# Badge_V3.net
KiCad netlist of a schematic drawn in EAGLE
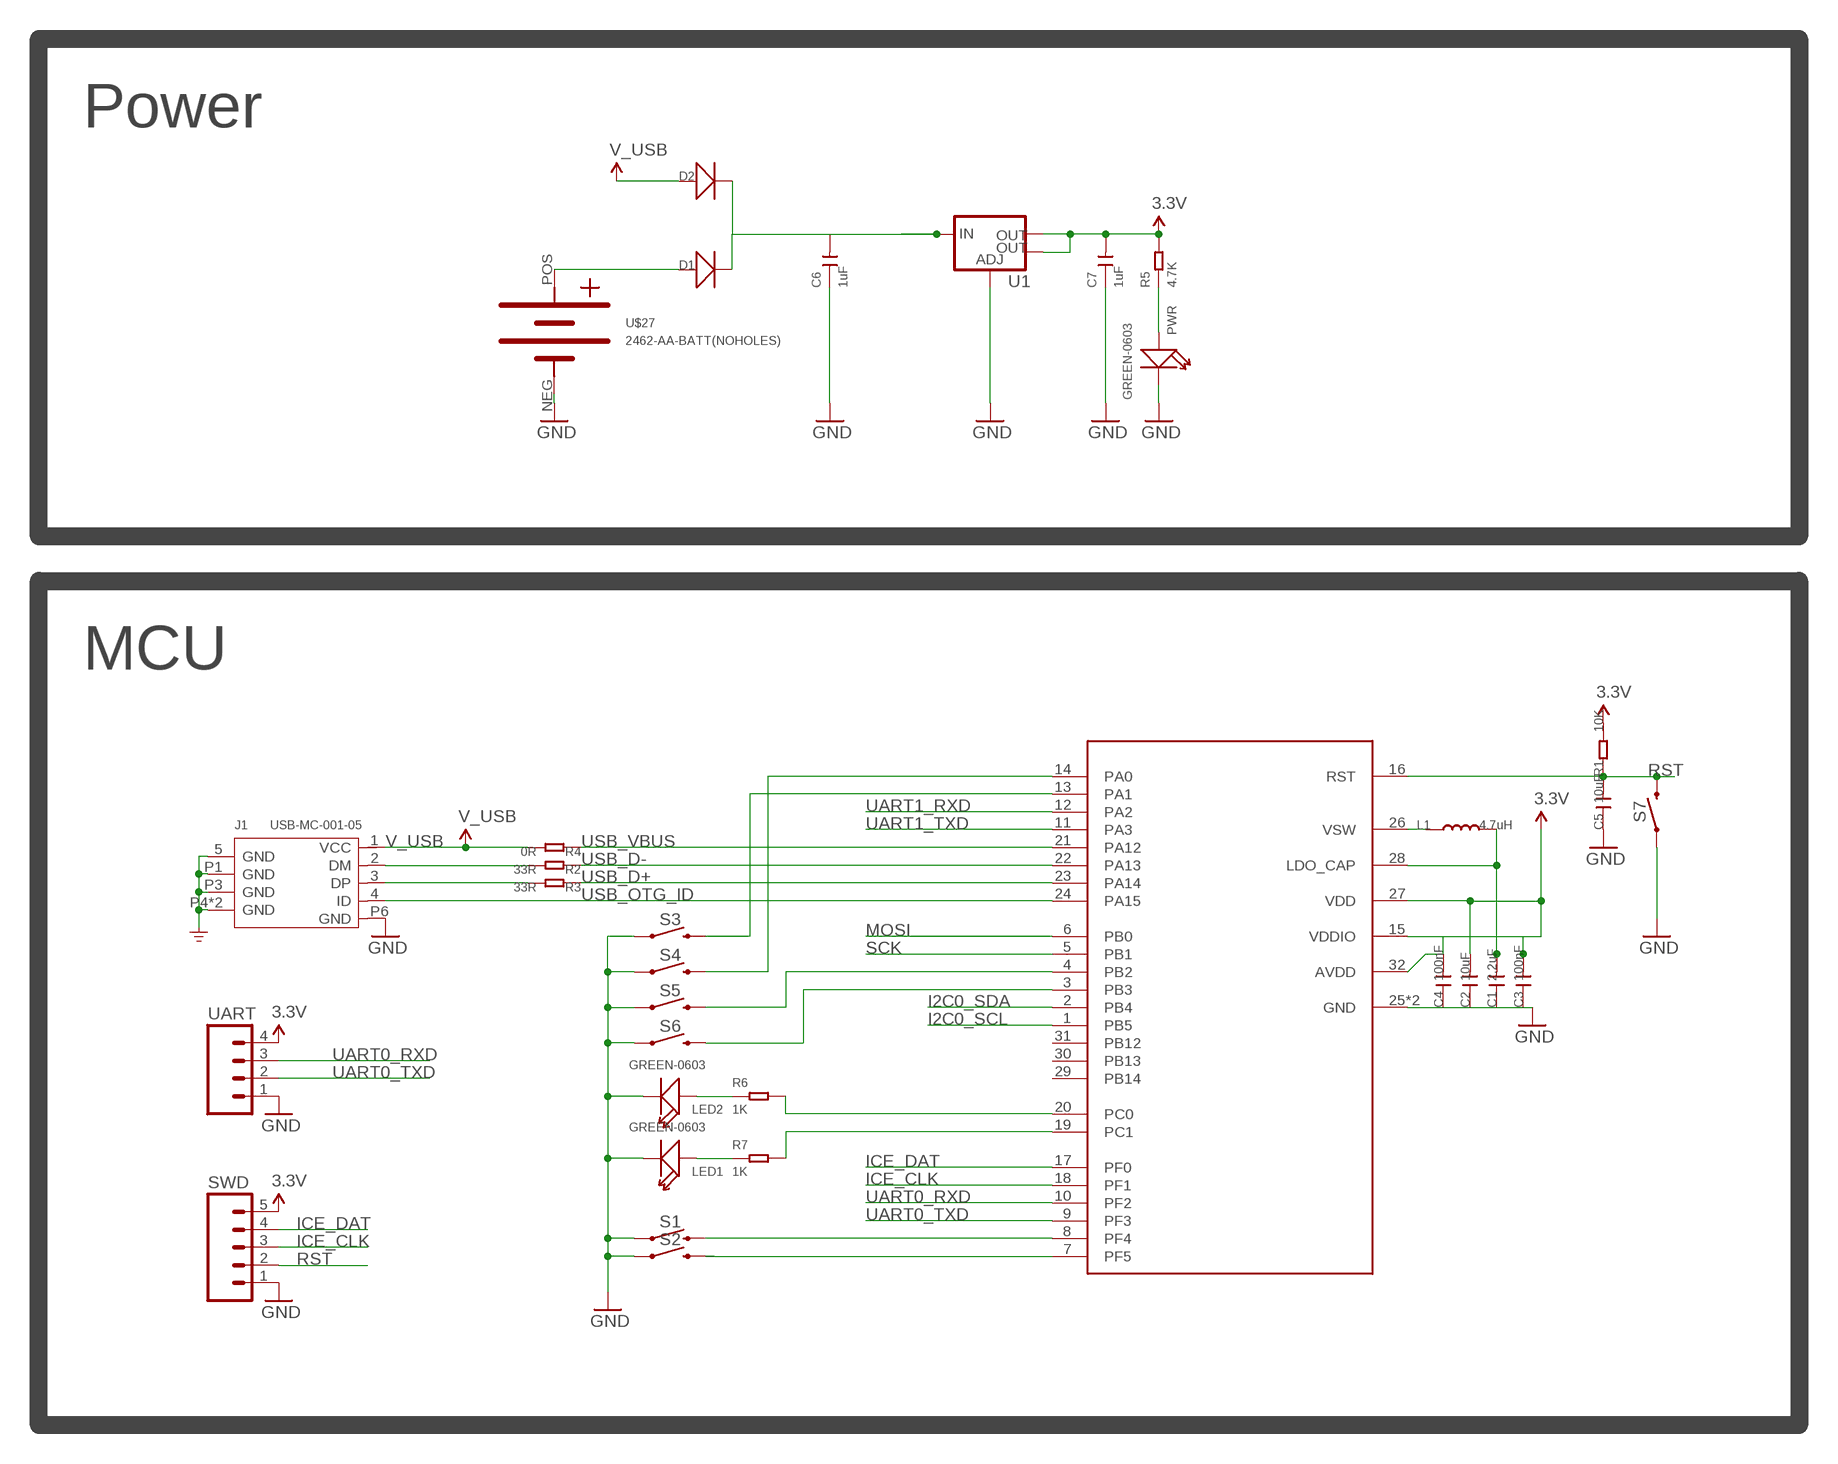
[diagram p0: schematic, sheet 1, part 1 of 2]
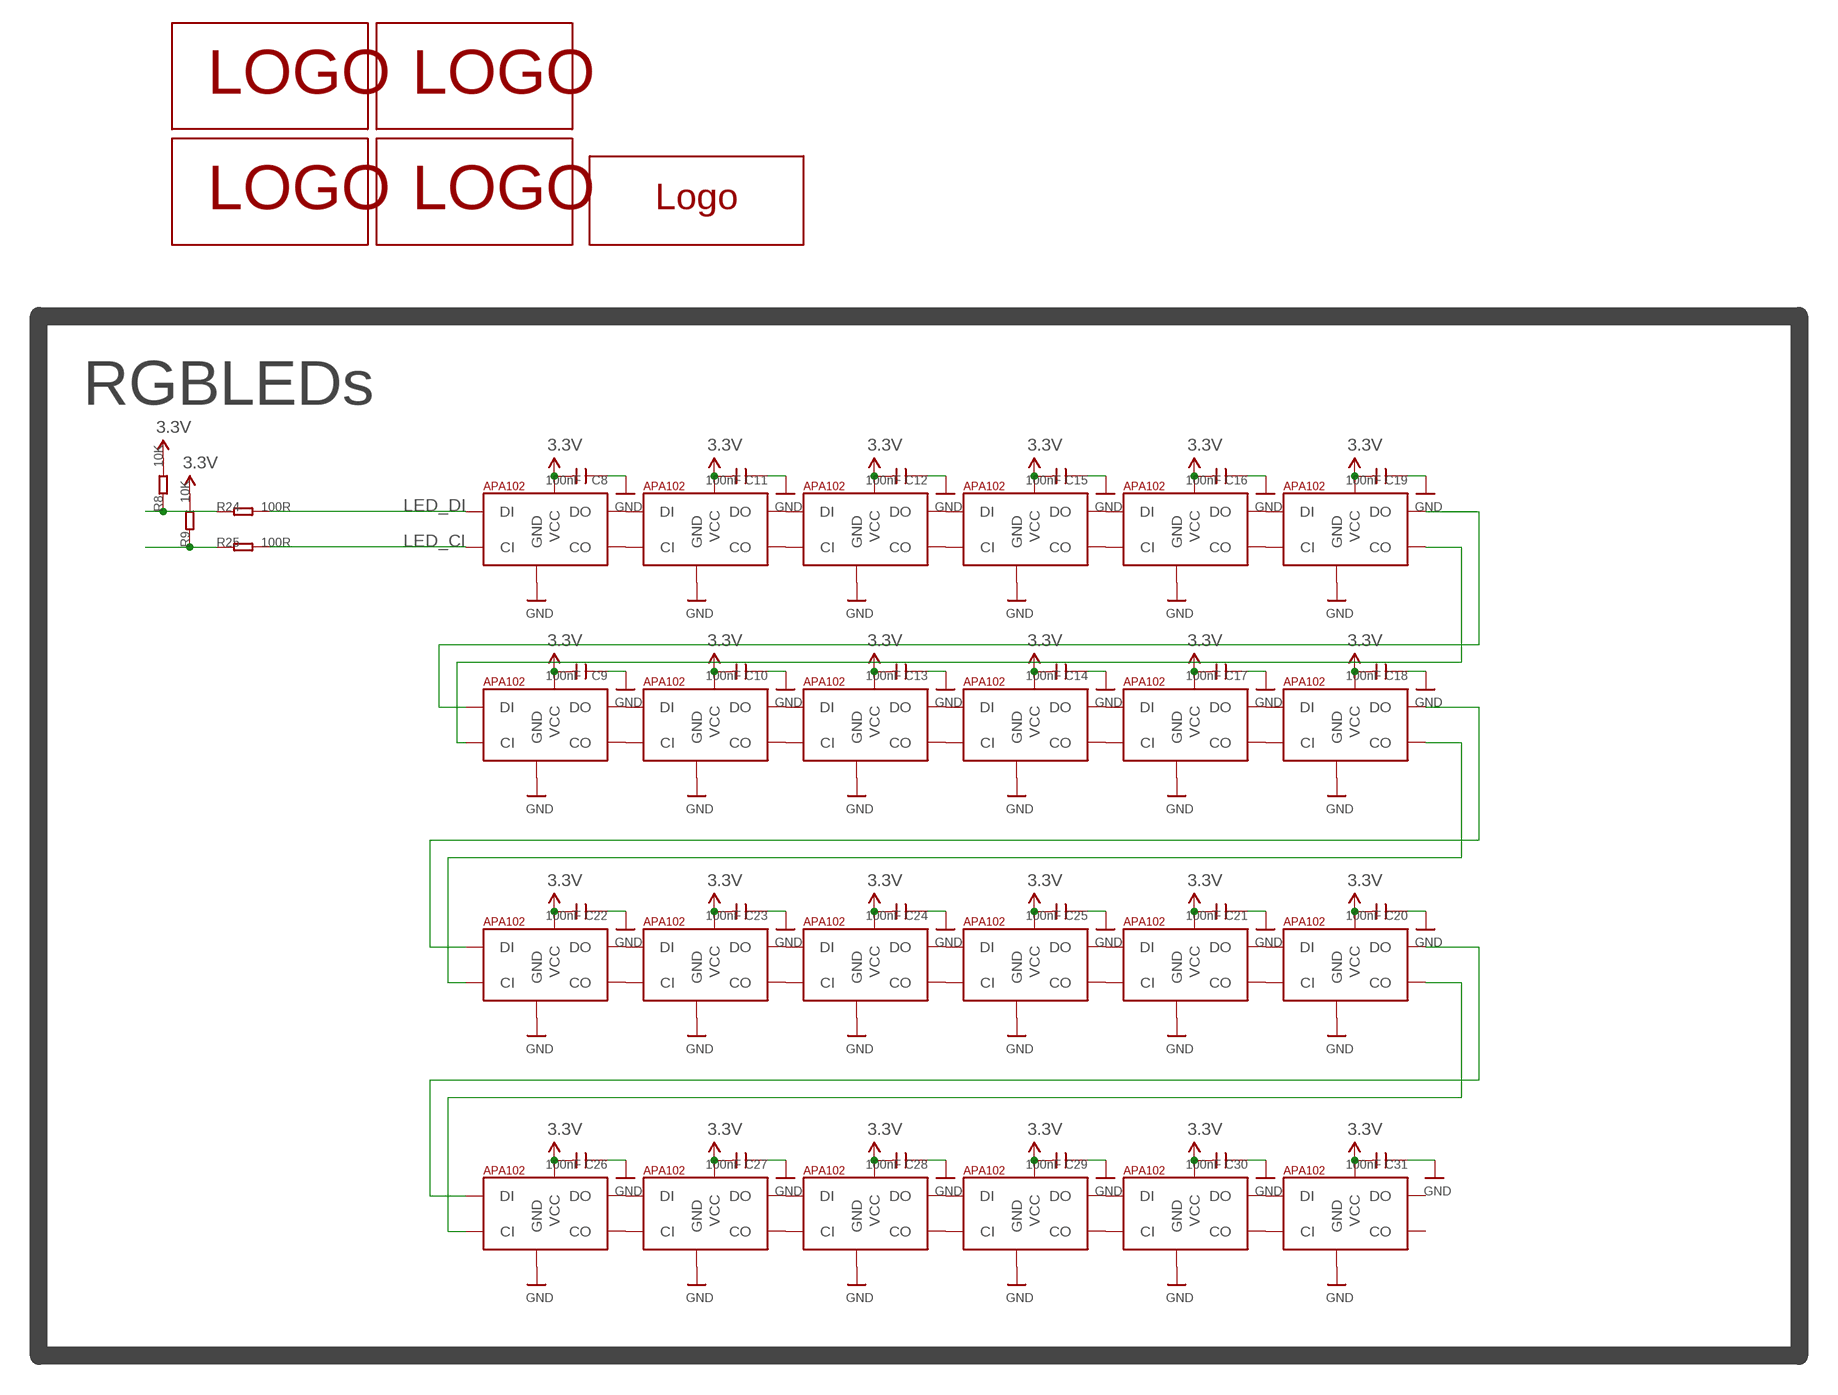
[diagram p1: schematic, sheet 1, part 2 of 2]

(export (version "E")
  (design (tool "Eeschema 10.0.6"))
  (components
    (comp (ref "C1")
      (value "2.2uF")
      (footprint "eagle-import:C0402@1")
      (libsource (lib "eagle-import") (part "C-0402"))
    )
    (comp (ref "C2")
      (value "10uF")
      (footprint "eagle-import:C0402@1")
      (libsource (lib "eagle-import") (part "C-0402"))
    )
    (comp (ref "C3")
      (value "100nF")
      (footprint "eagle-import:C0603@1")
      (libsource (lib "eagle-import") (part "C-0603"))
    )
    (comp (ref "C4")
      (value "100nF")
      (footprint "eagle-import:C0402@1")
      (libsource (lib "eagle-import") (part "C-0402"))
    )
    (comp (ref "C5")
      (value "10uF")
      (footprint "eagle-import:C0402@1")
      (libsource (lib "eagle-import") (part "C-0402"))
    )
    (comp (ref "C6")
      (value "1uF")
      (footprint "eagle-import:C0603")
      (libsource (lib "eagle-import") (part "CAP-0603"))
    )
    (comp (ref "C7")
      (value "1uF")
      (footprint "eagle-import:C0603")
      (libsource (lib "eagle-import") (part "CAP-0603"))
    )
    (comp (ref "C8")
      (value "100nF")
      (footprint "eagle-import:C0402@1")
      (libsource (lib "eagle-import") (part "C-0402"))
    )
    (comp (ref "C9")
      (value "100nF")
      (footprint "eagle-import:C0402@1")
      (libsource (lib "eagle-import") (part "C-0402"))
    )
    (comp (ref "C10")
      (value "100nF")
      (footprint "eagle-import:C0402@1")
      (libsource (lib "eagle-import") (part "C-0402"))
    )
    (comp (ref "C11")
      (value "100nF")
      (footprint "eagle-import:C0402@1")
      (libsource (lib "eagle-import") (part "C-0402"))
    )
    (comp (ref "C12")
      (value "100nF")
      (footprint "eagle-import:C0402@1")
      (libsource (lib "eagle-import") (part "C-0402"))
    )
    (comp (ref "C13")
      (value "100nF")
      (footprint "eagle-import:C0402@1")
      (libsource (lib "eagle-import") (part "C-0402"))
    )
    (comp (ref "C14")
      (value "100nF")
      (footprint "eagle-import:C0402@1")
      (libsource (lib "eagle-import") (part "C-0402"))
    )
    (comp (ref "C15")
      (value "100nF")
      (footprint "eagle-import:C0402@1")
      (libsource (lib "eagle-import") (part "C-0402"))
    )
    (comp (ref "C16")
      (value "100nF")
      (footprint "eagle-import:C0402@1")
      (libsource (lib "eagle-import") (part "C-0402"))
    )
    (comp (ref "C17")
      (value "100nF")
      (footprint "eagle-import:C0402@1")
      (libsource (lib "eagle-import") (part "C-0402"))
    )
    (comp (ref "C18")
      (value "100nF")
      (footprint "eagle-import:C0402@1")
      (libsource (lib "eagle-import") (part "C-0402"))
    )
    (comp (ref "C19")
      (value "100nF")
      (footprint "eagle-import:C0402@1")
      (libsource (lib "eagle-import") (part "C-0402"))
    )
    (comp (ref "C20")
      (value "100nF")
      (footprint "eagle-import:C0402@1")
      (libsource (lib "eagle-import") (part "C-0402"))
    )
    (comp (ref "C21")
      (value "100nF")
      (footprint "eagle-import:C0402@1")
      (libsource (lib "eagle-import") (part "C-0402"))
    )
    (comp (ref "C22")
      (value "100nF")
      (footprint "eagle-import:C0402@1")
      (libsource (lib "eagle-import") (part "C-0402"))
    )
    (comp (ref "C23")
      (value "100nF")
      (footprint "eagle-import:C0402@1")
      (libsource (lib "eagle-import") (part "C-0402"))
    )
    (comp (ref "C24")
      (value "100nF")
      (footprint "eagle-import:C0402@1")
      (libsource (lib "eagle-import") (part "C-0402"))
    )
    (comp (ref "C25")
      (value "100nF")
      (footprint "eagle-import:C0402@1")
      (libsource (lib "eagle-import") (part "C-0402"))
    )
    (comp (ref "C26")
      (value "100nF")
      (footprint "eagle-import:C0402@1")
      (libsource (lib "eagle-import") (part "C-0402"))
    )
    (comp (ref "C27")
      (value "100nF")
      (footprint "eagle-import:C0402@1")
      (libsource (lib "eagle-import") (part "C-0402"))
    )
    (comp (ref "C28")
      (value "100nF")
      (footprint "eagle-import:C0402@1")
      (libsource (lib "eagle-import") (part "C-0402"))
    )
    (comp (ref "C29")
      (value "100nF")
      (footprint "eagle-import:C0402@1")
      (libsource (lib "eagle-import") (part "C-0402"))
    )
    (comp (ref "C30")
      (value "100nF")
      (footprint "eagle-import:C0402@1")
      (libsource (lib "eagle-import") (part "C-0402"))
    )
    (comp (ref "C31")
      (value "100nF")
      (footprint "eagle-import:C0402@1")
      (libsource (lib "eagle-import") (part "C-0402"))
    )
    (comp (ref "D1")
      (value "D'1206'")
      (footprint "eagle-import:SOD123")
      (libsource (lib "eagle-import") (part "D'1206'"))
    )
    (comp (ref "D2")
      (value "D'1206'")
      (footprint "eagle-import:SOD123")
      (libsource (lib "eagle-import") (part "D'1206'"))
    )
    (comp (ref "J1")
      (value "USB-MC-001-05")
      (footprint "eagle-import:MICRO-USB5+5P-SMD-0.65-7.2X5.06MM")
      (libsource (lib "eagle-import") (part "MICRO-USB5+4P"))
    )
    (comp (ref "L1")
      (value "4.7uH")
      (footprint "eagle-import:L0603")
      (libsource (lib "eagle-import") (part "L'0603'"))
    )
    (comp (ref "LED1")
      (value "GREEN-0603")
      (footprint "eagle-import:LED-0603")
      (fields (field (name "MPN") "19-217-G7C-AN1P2-3T"))
      (libsource (lib "eagle-import") (part "SMD-LED-CLEAR-GREEN(0603)"))
    )
    (comp (ref "LED2")
      (value "GREEN-0603")
      (footprint "eagle-import:LED-0603")
      (fields (field (name "MPN") "19-217-G7C-AN1P2-3T"))
      (libsource (lib "eagle-import") (part "SMD-LED-CLEAR-GREEN(0603)"))
    )
    (comp (ref "PWR")
      (value "GREEN-0603")
      (footprint "eagle-import:LED-0603")
      (fields (field (name "MPN") "19-217-G7C-AN1P2-3T"))
      (libsource (lib "eagle-import") (part "SMD-LED-CLEAR-GREEN(0603)"))
    )
    (comp (ref "R1")
      (value "10K")
      (footprint "eagle-import:R0402")
      (libsource (lib "eagle-import") (part "R-0402"))
    )
    (comp (ref "R2")
      (value "33R")
      (footprint "eagle-import:R0402")
      (libsource (lib "eagle-import") (part "R-0402"))
    )
    (comp (ref "R3")
      (value "33R")
      (footprint "eagle-import:R0402")
      (libsource (lib "eagle-import") (part "R-0402"))
    )
    (comp (ref "R4")
      (value "0R")
      (footprint "eagle-import:R0402")
      (libsource (lib "eagle-import") (part "R-0402"))
    )
    (comp (ref "R5")
      (value "4.7K")
      (footprint "eagle-import:R0402")
      (libsource (lib "eagle-import") (part "RES-0402"))
    )
    (comp (ref "R6")
      (value "1K")
      (footprint "eagle-import:R0402")
      (libsource (lib "eagle-import") (part "RES-0402"))
    )
    (comp (ref "R7")
      (value "1K")
      (footprint "eagle-import:R0402")
      (libsource (lib "eagle-import") (part "RES-0402"))
    )
    (comp (ref "R8")
      (value "10K")
      (footprint "eagle-import:R0402")
      (libsource (lib "eagle-import") (part "R-0402"))
    )
    (comp (ref "R9")
      (value "10K")
      (footprint "eagle-import:R0402")
      (libsource (lib "eagle-import") (part "R-0402"))
    )
    (comp (ref "R24")
      (value "100R")
      (footprint "eagle-import:R0402")
      (libsource (lib "eagle-import") (part "R-0402"))
    )
    (comp (ref "R25")
      (value "100R")
      (footprint "eagle-import:R0402")
      (libsource (lib "eagle-import") (part "R-0402"))
    )
    (comp (ref "S1")
      (value "MOMENTARY-SWITCH-SPST-SMD-6.2MM-TALL")
      (footprint "eagle-import:TACTILE_SWITCH_SMD_6.2MM_TALL")
      (libsource (lib "eagle-import") (part "MOMENTARY-SWITCH-SPST-SMD-6.2MM-TALL"))
    )
    (comp (ref "S2")
      (value "MOMENTARY-SWITCH-SPST-SMD-6.2MM-TALL")
      (footprint "eagle-import:TACTILE_SWITCH_SMD_6.2MM_TALL")
      (libsource (lib "eagle-import") (part "MOMENTARY-SWITCH-SPST-SMD-6.2MM-TALL"))
    )
    (comp (ref "S3")
      (value "MOMENTARY-SWITCH-SPST-SMD-6.2MM-TALL")
      (footprint "eagle-import:TACTILE_SWITCH_SMD_6.2MM_TALL")
      (libsource (lib "eagle-import") (part "MOMENTARY-SWITCH-SPST-SMD-6.2MM-TALL"))
    )
    (comp (ref "S4")
      (value "MOMENTARY-SWITCH-SPST-SMD-6.2MM-TALL")
      (footprint "eagle-import:TACTILE_SWITCH_SMD_6.2MM_TALL")
      (libsource (lib "eagle-import") (part "MOMENTARY-SWITCH-SPST-SMD-6.2MM-TALL"))
    )
    (comp (ref "S5")
      (value "MOMENTARY-SWITCH-SPST-SMD-6.2MM-TALL")
      (footprint "eagle-import:TACTILE_SWITCH_SMD_6.2MM_TALL")
      (libsource (lib "eagle-import") (part "MOMENTARY-SWITCH-SPST-SMD-6.2MM-TALL"))
    )
    (comp (ref "S6")
      (value "MOMENTARY-SWITCH-SPST-SMD-6.2MM-TALL")
      (footprint "eagle-import:TACTILE_SWITCH_SMD_6.2MM_TALL")
      (libsource (lib "eagle-import") (part "MOMENTARY-SWITCH-SPST-SMD-6.2MM-TALL"))
    )
    (comp (ref "S7")
      (value "MOMENTARY-SWITCH-SPST-SMD-6.2MM-TALL")
      (footprint "eagle-import:TACTILE_SWITCH_SMD_6.2MM_TALL")
      (libsource (lib "eagle-import") (part "MOMENTARY-SWITCH-SPST-SMD-6.2MM-TALL"))
    )
    (comp (ref "SWD")
      (value "M05LOCK")
      (footprint "eagle-import:1X05_LOCK")
      (libsource (lib "eagle-import") (part "M05LOCK"))
    )
    (comp (ref "U$1")
      (value "M2351")
      (footprint "eagle-import:QFN-32")
      (libsource (lib "eagle-import") (part "M2351"))
    )
    (comp (ref "U$2")
      (value "APA1022020")
      (footprint "eagle-import:APA102_2020")
      (libsource (lib "eagle-import") (part "APA1022020"))
    )
    (comp (ref "U$4")
      (value "APA1022020")
      (footprint "eagle-import:APA102_2020")
      (libsource (lib "eagle-import") (part "APA1022020"))
    )
    (comp (ref "U$5")
      (value "APA1022020")
      (footprint "eagle-import:APA102_2020")
      (libsource (lib "eagle-import") (part "APA1022020"))
    )
    (comp (ref "U$6")
      (value "APA1022020")
      (footprint "eagle-import:APA102_2020")
      (libsource (lib "eagle-import") (part "APA1022020"))
    )
    (comp (ref "U$7")
      (value "APA1022020")
      (footprint "eagle-import:APA102_2020")
      (libsource (lib "eagle-import") (part "APA1022020"))
    )
    (comp (ref "U$8")
      (value "APA1022020")
      (footprint "eagle-import:APA102_2020")
      (libsource (lib "eagle-import") (part "APA1022020"))
    )
    (comp (ref "U$9")
      (value "APA1022020")
      (footprint "eagle-import:APA102_2020")
      (libsource (lib "eagle-import") (part "APA1022020"))
    )
    (comp (ref "U$10")
      (value "APA1022020")
      (footprint "eagle-import:APA102_2020")
      (libsource (lib "eagle-import") (part "APA1022020"))
    )
    (comp (ref "U$11")
      (value "APA1022020")
      (footprint "eagle-import:APA102_2020")
      (libsource (lib "eagle-import") (part "APA1022020"))
    )
    (comp (ref "U$12")
      (value "APA1022020")
      (footprint "eagle-import:APA102_2020")
      (libsource (lib "eagle-import") (part "APA1022020"))
    )
    (comp (ref "U$13")
      (value "APA1022020")
      (footprint "eagle-import:APA102_2020")
      (libsource (lib "eagle-import") (part "APA1022020"))
    )
    (comp (ref "U$14")
      (value "APA1022020")
      (footprint "eagle-import:APA102_2020")
      (libsource (lib "eagle-import") (part "APA1022020"))
    )
    (comp (ref "U$15")
      (value "APA1022020")
      (footprint "eagle-import:APA102_2020")
      (libsource (lib "eagle-import") (part "APA1022020"))
    )
    (comp (ref "U$16")
      (value "APA1022020")
      (footprint "eagle-import:APA102_2020")
      (libsource (lib "eagle-import") (part "APA1022020"))
    )
    (comp (ref "U$17")
      (value "APA1022020")
      (footprint "eagle-import:APA102_2020")
      (libsource (lib "eagle-import") (part "APA1022020"))
    )
    (comp (ref "U$18")
      (value "APA1022020")
      (footprint "eagle-import:APA102_2020")
      (libsource (lib "eagle-import") (part "APA1022020"))
    )
    (comp (ref "U$19")
      (value "APA1022020")
      (footprint "eagle-import:APA102_2020")
      (libsource (lib "eagle-import") (part "APA1022020"))
    )
    (comp (ref "U$20")
      (value "APA1022020")
      (footprint "eagle-import:APA102_2020")
      (libsource (lib "eagle-import") (part "APA1022020"))
    )
    (comp (ref "U$21")
      (value "APA1022020")
      (footprint "eagle-import:APA102_2020")
      (libsource (lib "eagle-import") (part "APA1022020"))
    )
    (comp (ref "U$22")
      (value "APA1022020")
      (footprint "eagle-import:APA102_2020")
      (libsource (lib "eagle-import") (part "APA1022020"))
    )
    (comp (ref "U$23")
      (value "APA1022020")
      (footprint "eagle-import:APA102_2020")
      (libsource (lib "eagle-import") (part "APA1022020"))
    )
    (comp (ref "U$24")
      (value "APA1022020")
      (footprint "eagle-import:APA102_2020")
      (libsource (lib "eagle-import") (part "APA1022020"))
    )
    (comp (ref "U$25")
      (value "APA1022020")
      (footprint "eagle-import:APA102_2020")
      (libsource (lib "eagle-import") (part "APA1022020"))
    )
    (comp (ref "U$26")
      (value "TAIWANSILK_FILL")
      (footprint "eagle-import:TAIWAN_SILK_FILL")
      (libsource (lib "eagle-import") (part "TAIWANSILK_FILL"))
    )
    (comp (ref "U$27")
      (value "2462-AA-BATT(NOHOLES)")
      (footprint "eagle-import:2462-AA-BATT-NOHOLES")
      (libsource (lib "eagle-import") (part "2462-AA-BATT(NOHOLES)"))
    )
    (comp (ref "U$28")
      (value "HITCON_LOGOGOLD_LARGE")
      (footprint "eagle-import:HITCON_LOGO_BIGGER_GOLD")
      (libsource (lib "eagle-import") (part "HITCON_LOGOGOLD_LARGE"))
    )
    (comp (ref "U$30")
      (value "TAIWANKIM")
      (footprint "eagle-import:TAIWAN_SILK_FILL_2")
      (libsource (lib "eagle-import") (part "TAIWANKIM"))
    )
    (comp (ref "U$31")
      (value "TAIWANMAZ")
      (footprint "eagle-import:TAIWAN_SILK_FILL_4")
      (libsource (lib "eagle-import") (part "TAIWANMAZ"))
    )
    (comp (ref "U$33")
      (value "APA1022020")
      (footprint "eagle-import:APA102_2020")
      (libsource (lib "eagle-import") (part "APA1022020"))
    )
    (comp (ref "U$34")
      (value "TAIWANPUN")
      (footprint "eagle-import:TAIWAN_SILK_FILL_3")
      (libsource (lib "eagle-import") (part "TAIWANPUN"))
    )
    (comp (ref "U1")
      (value "V_REG_LM1117SOT223")
      (footprint "eagle-import:SOT223")
      (libsource (lib "eagle-import") (part "V_REG_LM1117SOT223"))
    )
    (comp (ref "UART")
      (value "M04LOCK")
      (footprint "eagle-import:1X04_LOCK")
      (libsource (lib "eagle-import") (part "M04LOCK"))
    )
  )
  (nets
    (net (code "1") (name "/I2C0_SCL") (class "Default")
      (node (ref "U$1") (pin "1") (pinfunction "PB5_1") (pintype "bidirectional"))
    )
    (net (code "2") (name "/I2C0_SDA") (class "Default")
      (node (ref "U$1") (pin "2") (pinfunction "PB4_2") (pintype "bidirectional"))
    )
    (net (code "3") (name "/ICE_CLK") (class "Default")
      (node (ref "SWD") (pin "3") (pinfunction "3_3") (pintype "passive"))
      (node (ref "U$1") (pin "18") (pinfunction "PF1_18") (pintype "bidirectional"))
    )
    (net (code "4") (name "/ICE_DAT") (class "Default")
      (node (ref "SWD") (pin "4") (pinfunction "4_4") (pintype "passive"))
      (node (ref "U$1") (pin "17") (pinfunction "PF0_17") (pintype "bidirectional"))
    )
    (net (code "5") (name "/LED_CI") (class "Default")
      (node (ref "R25") (pin "2") (pinfunction "2_2") (pintype "passive"))
      (node (ref "U$33") (pin "C_IN") (pinfunction "CI_C_IN") (pintype "bidirectional"))
    )
    (net (code "6") (name "/LED_DI") (class "Default")
      (node (ref "R24") (pin "2") (pinfunction "2_2") (pintype "passive"))
      (node (ref "U$33") (pin "D_IN") (pinfunction "DI_D_IN") (pintype "bidirectional"))
    )
    (net (code "7") (name "/MOSI") (class "Default")
      (node (ref "R24") (pin "1") (pinfunction "1_1") (pintype "passive"))
      (node (ref "R8") (pin "1") (pinfunction "1_1") (pintype "passive"))
      (node (ref "U$1") (pin "6") (pinfunction "PB0_6") (pintype "bidirectional"))
    )
    (net (code "8") (name "/RST") (class "Default")
      (node (ref "C5") (pin "2") (pinfunction "2_2") (pintype "passive"))
      (node (ref "R1") (pin "1") (pinfunction "1_1") (pintype "passive"))
      (node (ref "S7") (pin "B2") (pinfunction "2_B2") (pintype "passive"))
      (node (ref "SWD") (pin "2") (pinfunction "2_2") (pintype "passive"))
      (node (ref "U$1") (pin "16") (pinfunction "RST_16") (pintype "bidirectional"))
    )
    (net (code "9") (name "/SCK") (class "Default")
      (node (ref "R25") (pin "1") (pinfunction "1_1") (pintype "passive"))
      (node (ref "R9") (pin "1") (pinfunction "1_1") (pintype "passive"))
      (node (ref "U$1") (pin "5") (pinfunction "PB1_5") (pintype "bidirectional"))
    )
    (net (code "10") (name "/UART0_RXD") (class "Default")
      (node (ref "U$1") (pin "10") (pinfunction "PF2_10") (pintype "bidirectional"))
      (node (ref "UART") (pin "3") (pinfunction "3_3") (pintype "passive"))
    )
    (net (code "11") (name "/UART0_TXD") (class "Default")
      (node (ref "U$1") (pin "9") (pinfunction "PF3_9") (pintype "bidirectional"))
      (node (ref "UART") (pin "2") (pinfunction "2_2") (pintype "passive"))
    )
    (net (code "12") (name "/UART1_RXD") (class "Default")
      (node (ref "U$1") (pin "12") (pinfunction "PA2_12") (pintype "bidirectional"))
    )
    (net (code "13") (name "/UART1_TXD") (class "Default")
      (node (ref "U$1") (pin "11") (pinfunction "PA3_11") (pintype "bidirectional"))
    )
    (net (code "14") (name "/USB_D+") (class "Default")
      (node (ref "R3") (pin "1") (pinfunction "1_1") (pintype "passive"))
      (node (ref "U$1") (pin "23") (pinfunction "PA14_23") (pintype "bidirectional"))
    )
    (net (code "15") (name "/USB_D-") (class "Default")
      (node (ref "R2") (pin "1") (pinfunction "1_1") (pintype "passive"))
      (node (ref "U$1") (pin "22") (pinfunction "PA13_22") (pintype "bidirectional"))
    )
    (net (code "16") (name "/USB_OTG_ID") (class "Default")
      (node (ref "J1") (pin "4") (pinfunction "ID_4") (pintype "bidirectional"))
      (node (ref "U$1") (pin "24") (pinfunction "PA15_24") (pintype "bidirectional"))
    )
    (net (code "17") (name "/USB_VBUS") (class "Default")
      (node (ref "R4") (pin "1") (pinfunction "1_1") (pintype "passive"))
      (node (ref "U$1") (pin "21") (pinfunction "PA12_21") (pintype "bidirectional"))
    )
    (net (code "18") (name "3.3V") (class "Default")
      (node (ref "C10") (pin "2") (pinfunction "2_2") (pintype "passive"))
      (node (ref "C11") (pin "2") (pinfunction "2_2") (pintype "passive"))
      (node (ref "C12") (pin "2") (pinfunction "2_2") (pintype "passive"))
      (node (ref "C13") (pin "2") (pinfunction "2_2") (pintype "passive"))
      (node (ref "C14") (pin "2") (pinfunction "2_2") (pintype "passive"))
      (node (ref "C15") (pin "2") (pinfunction "2_2") (pintype "passive"))
      (node (ref "C16") (pin "2") (pinfunction "2_2") (pintype "passive"))
      (node (ref "C17") (pin "2") (pinfunction "2_2") (pintype "passive"))
      (node (ref "C18") (pin "2") (pinfunction "2_2") (pintype "passive"))
      (node (ref "C19") (pin "2") (pinfunction "2_2") (pintype "passive"))
      (node (ref "C2") (pin "2") (pinfunction "2_2") (pintype "passive"))
      (node (ref "C20") (pin "2") (pinfunction "2_2") (pintype "passive"))
      (node (ref "C21") (pin "2") (pinfunction "2_2") (pintype "passive"))
      (node (ref "C22") (pin "2") (pinfunction "2_2") (pintype "passive"))
      (node (ref "C23") (pin "2") (pinfunction "2_2") (pintype "passive"))
      (node (ref "C24") (pin "2") (pinfunction "2_2") (pintype "passive"))
      (node (ref "C25") (pin "2") (pinfunction "2_2") (pintype "passive"))
      (node (ref "C26") (pin "2") (pinfunction "2_2") (pintype "passive"))
      (node (ref "C27") (pin "2") (pinfunction "2_2") (pintype "passive"))
      (node (ref "C28") (pin "2") (pinfunction "2_2") (pintype "passive"))
      (node (ref "C29") (pin "2") (pinfunction "2_2") (pintype "passive"))
      (node (ref "C3") (pin "2") (pinfunction "2_2") (pintype "passive"))
      (node (ref "C30") (pin "2") (pinfunction "2_2") (pintype "passive"))
      (node (ref "C31") (pin "2") (pinfunction "2_2") (pintype "passive"))
      (node (ref "C4") (pin "2") (pinfunction "2_2") (pintype "passive"))
      (node (ref "C7") (pin "2") (pinfunction "2_2") (pintype "passive"))
      (node (ref "C8") (pin "2") (pinfunction "2_2") (pintype "passive"))
      (node (ref "C9") (pin "2") (pinfunction "2_2") (pintype "passive"))
      (node (ref "R1") (pin "2") (pinfunction "2_2") (pintype "passive"))
      (node (ref "R5") (pin "2") (pinfunction "2_2") (pintype "passive"))
      (node (ref "R8") (pin "2") (pinfunction "2_2") (pintype "passive"))
      (node (ref "R9") (pin "2") (pinfunction "2_2") (pintype "passive"))
      (node (ref "SWD") (pin "5") (pinfunction "5_5") (pintype "passive"))
      (node (ref "U$1") (pin "15") (pinfunction "VDDIO_15") (pintype "bidirectional"))
      (node (ref "U$1") (pin "27") (pinfunction "VDD_27") (pintype "bidirectional"))
      (node (ref "U$1") (pin "32") (pinfunction "AVDD_32") (pintype "bidirectional"))
      (node (ref "U$10") (pin "V_CC") (pinfunction "VCC_V_CC") (pintype "bidirectional"))
      (node (ref "U$11") (pin "V_CC") (pinfunction "VCC_V_CC") (pintype "bidirectional"))
      (node (ref "U$12") (pin "V_CC") (pinfunction "VCC_V_CC") (pintype "bidirectional"))
      (node (ref "U$13") (pin "V_CC") (pinfunction "VCC_V_CC") (pintype "bidirectional"))
      (node (ref "U$14") (pin "V_CC") (pinfunction "VCC_V_CC") (pintype "bidirectional"))
      (node (ref "U$15") (pin "V_CC") (pinfunction "VCC_V_CC") (pintype "bidirectional"))
      (node (ref "U$16") (pin "V_CC") (pinfunction "VCC_V_CC") (pintype "bidirectional"))
      (node (ref "U$17") (pin "V_CC") (pinfunction "VCC_V_CC") (pintype "bidirectional"))
      (node (ref "U$18") (pin "V_CC") (pinfunction "VCC_V_CC") (pintype "bidirectional"))
      (node (ref "U$19") (pin "V_CC") (pinfunction "VCC_V_CC") (pintype "bidirectional"))
      (node (ref "U$2") (pin "V_CC") (pinfunction "VCC_V_CC") (pintype "bidirectional"))
      (node (ref "U$20") (pin "V_CC") (pinfunction "VCC_V_CC") (pintype "bidirectional"))
      (node (ref "U$21") (pin "V_CC") (pinfunction "VCC_V_CC") (pintype "bidirectional"))
      (node (ref "U$22") (pin "V_CC") (pinfunction "VCC_V_CC") (pintype "bidirectional"))
      (node (ref "U$23") (pin "V_CC") (pinfunction "VCC_V_CC") (pintype "bidirectional"))
      (node (ref "U$24") (pin "V_CC") (pinfunction "VCC_V_CC") (pintype "bidirectional"))
      (node (ref "U$25") (pin "V_CC") (pinfunction "VCC_V_CC") (pintype "bidirectional"))
      (node (ref "U$33") (pin "V_CC") (pinfunction "VCC_V_CC") (pintype "bidirectional"))
      (node (ref "U$4") (pin "V_CC") (pinfunction "VCC_V_CC") (pintype "bidirectional"))
      (node (ref "U$5") (pin "V_CC") (pinfunction "VCC_V_CC") (pintype "bidirectional"))
      (node (ref "U$6") (pin "V_CC") (pinfunction "VCC_V_CC") (pintype "bidirectional"))
      (node (ref "U$7") (pin "V_CC") (pinfunction "VCC_V_CC") (pintype "bidirectional"))
      (node (ref "U$8") (pin "V_CC") (pinfunction "VCC_V_CC") (pintype "bidirectional"))
      (node (ref "U$9") (pin "V_CC") (pinfunction "VCC_V_CC") (pintype "bidirectional"))
      (node (ref "U1") (pin "2") (pinfunction "OUT_2") (pintype "output"))
      (node (ref "U1") (pin "4") (pinfunction "OUT_4") (pintype "output"))
      (node (ref "UART") (pin "4") (pinfunction "4_4") (pintype "passive"))
    )
    (net (code "19") (name "GND") (class "Default")
      (node (ref "C1") (pin "1") (pinfunction "1_1") (pintype "passive"))
      (node (ref "C10") (pin "1") (pinfunction "1_1") (pintype "passive"))
      (node (ref "C11") (pin "1") (pinfunction "1_1") (pintype "passive"))
      (node (ref "C12") (pin "1") (pinfunction "1_1") (pintype "passive"))
      (node (ref "C13") (pin "1") (pinfunction "1_1") (pintype "passive"))
      (node (ref "C14") (pin "1") (pinfunction "1_1") (pintype "passive"))
      (node (ref "C15") (pin "1") (pinfunction "1_1") (pintype "passive"))
      (node (ref "C16") (pin "1") (pinfunction "1_1") (pintype "passive"))
      (node (ref "C17") (pin "1") (pinfunction "1_1") (pintype "passive"))
      (node (ref "C18") (pin "1") (pinfunction "1_1") (pintype "passive"))
      (node (ref "C19") (pin "1") (pinfunction "1_1") (pintype "passive"))
      (node (ref "C2") (pin "1") (pinfunction "1_1") (pintype "passive"))
      (node (ref "C20") (pin "1") (pinfunction "1_1") (pintype "passive"))
      (node (ref "C21") (pin "1") (pinfunction "1_1") (pintype "passive"))
      (node (ref "C22") (pin "1") (pinfunction "1_1") (pintype "passive"))
      (node (ref "C23") (pin "1") (pinfunction "1_1") (pintype "passive"))
      (node (ref "C24") (pin "1") (pinfunction "1_1") (pintype "passive"))
      (node (ref "C25") (pin "1") (pinfunction "1_1") (pintype "passive"))
      (node (ref "C26") (pin "1") (pinfunction "1_1") (pintype "passive"))
      (node (ref "C27") (pin "1") (pinfunction "1_1") (pintype "passive"))
      (node (ref "C28") (pin "1") (pinfunction "1_1") (pintype "passive"))
      (node (ref "C29") (pin "1") (pinfunction "1_1") (pintype "passive"))
      (node (ref "C3") (pin "1") (pinfunction "1_1") (pintype "passive"))
      (node (ref "C30") (pin "1") (pinfunction "1_1") (pintype "passive"))
      (node (ref "C31") (pin "1") (pinfunction "1_1") (pintype "passive"))
      (node (ref "C4") (pin "1") (pinfunction "1_1") (pintype "passive"))
      (node (ref "C5") (pin "1") (pinfunction "1_1") (pintype "passive"))
      (node (ref "C6") (pin "1") (pinfunction "1_1") (pintype "passive"))
      (node (ref "C7") (pin "1") (pinfunction "1_1") (pintype "passive"))
      (node (ref "C8") (pin "1") (pinfunction "1_1") (pintype "passive"))
      (node (ref "C9") (pin "1") (pinfunction "1_1") (pintype "passive"))
      (node (ref "J1") (pin "5") (pinfunction "GND_5") (pintype "bidirectional"))
      (node (ref "J1") (pin "P1") (pinfunction "GND_P1") (pintype "bidirectional"))
      (node (ref "J1") (pin "P3") (pinfunction "GND_P3") (pintype "bidirectional"))
      (node (ref "J1") (pin "P4") (pinfunction "GND_P4") (pintype "bidirectional"))
      (node (ref "J1") (pin "P5") (pinfunction "GND_P5") (pintype "bidirectional"))
      (node (ref "J1") (pin "P6") (pinfunction "GND_P6") (pintype "bidirectional"))
      (node (ref "LED1") (pin "-") (pinfunction "-_-") (pintype "passive"))
      (node (ref "LED2") (pin "-") (pinfunction "-_-") (pintype "passive"))
      (node (ref "PWR") (pin "-") (pinfunction "-_-") (pintype "passive"))
      (node (ref "S1") (pin "A2") (pinfunction "1_A2") (pintype "passive"))
      (node (ref "S2") (pin "A2") (pinfunction "1_A2") (pintype "passive"))
      (node (ref "S3") (pin "A2") (pinfunction "1_A2") (pintype "passive"))
      (node (ref "S4") (pin "A2") (pinfunction "1_A2") (pintype "passive"))
      (node (ref "S5") (pin "A2") (pinfunction "1_A2") (pintype "passive"))
      (node (ref "S6") (pin "A2") (pinfunction "1_A2") (pintype "passive"))
      (node (ref "S7") (pin "A2") (pinfunction "1_A2") (pintype "passive"))
      (node (ref "SWD") (pin "1") (pinfunction "1_1") (pintype "passive"))
      (node (ref "U$1") (pin "25") (pinfunction "GND_25") (pintype "bidirectional"))
      (node (ref "U$1") (pin "EP") (pinfunction "GND_EP") (pintype "bidirectional"))
      (node (ref "U$10") (pin "GND") (pinfunction "GND_GND") (pintype "bidirectional"))
      (node (ref "U$11") (pin "GND") (pinfunction "GND_GND") (pintype "bidirectional"))
      (node (ref "U$12") (pin "GND") (pinfunction "GND_GND") (pintype "bidirectional"))
      (node (ref "U$13") (pin "GND") (pinfunction "GND_GND") (pintype "bidirectional"))
      (node (ref "U$14") (pin "GND") (pinfunction "GND_GND") (pintype "bidirectional"))
      (node (ref "U$15") (pin "GND") (pinfunction "GND_GND") (pintype "bidirectional"))
      (node (ref "U$16") (pin "GND") (pinfunction "GND_GND") (pintype "bidirectional"))
      (node (ref "U$17") (pin "GND") (pinfunction "GND_GND") (pintype "bidirectional"))
      (node (ref "U$18") (pin "GND") (pinfunction "GND_GND") (pintype "bidirectional"))
      (node (ref "U$19") (pin "GND") (pinfunction "GND_GND") (pintype "bidirectional"))
      (node (ref "U$2") (pin "GND") (pinfunction "GND_GND") (pintype "bidirectional"))
      (node (ref "U$20") (pin "GND") (pinfunction "GND_GND") (pintype "bidirectional"))
      (node (ref "U$21") (pin "GND") (pinfunction "GND_GND") (pintype "bidirectional"))
      (node (ref "U$22") (pin "GND") (pinfunction "GND_GND") (pintype "bidirectional"))
      (node (ref "U$23") (pin "GND") (pinfunction "GND_GND") (pintype "bidirectional"))
      (node (ref "U$24") (pin "GND") (pinfunction "GND_GND") (pintype "bidirectional"))
      (node (ref "U$25") (pin "GND") (pinfunction "GND_GND") (pintype "bidirectional"))
      (node (ref "U$27") (pin "NEG") (pinfunction "NEG_NEG") (pintype "bidirectional"))
      (node (ref "U$33") (pin "GND") (pinfunction "GND_GND") (pintype "bidirectional"))
      (node (ref "U$4") (pin "GND") (pinfunction "GND_GND") (pintype "bidirectional"))
      (node (ref "U$5") (pin "GND") (pinfunction "GND_GND") (pintype "bidirectional"))
      (node (ref "U$6") (pin "GND") (pinfunction "GND_GND") (pintype "bidirectional"))
      (node (ref "U$7") (pin "GND") (pinfunction "GND_GND") (pintype "bidirectional"))
      (node (ref "U$8") (pin "GND") (pinfunction "GND_GND") (pintype "bidirectional"))
      (node (ref "U$9") (pin "GND") (pinfunction "GND_GND") (pintype "bidirectional"))
      (node (ref "U1") (pin "1") (pinfunction "ADJ_1") (pintype "input"))
      (node (ref "UART") (pin "1") (pinfunction "1_1") (pintype "passive"))
    )
    (net (code "20") (name "Net-(D1-Pad+)") (class "Default")
      (node (ref "D1") (pin "+") (pinfunction "+_+") (pintype "passive"))
      (node (ref "U$27") (pin "POS") (pinfunction "POS_POS") (pintype "bidirectional"))
    )
    (net (code "21") (name "Net-(J1-DM)") (class "Default")
      (node (ref "J1") (pin "2") (pinfunction "DM_2") (pintype "bidirectional"))
      (node (ref "R2") (pin "2") (pinfunction "2_2") (pintype "passive"))
    )
    (net (code "22") (name "Net-(J1-DP)") (class "Default")
      (node (ref "J1") (pin "3") (pinfunction "DP_3") (pintype "bidirectional"))
      (node (ref "R3") (pin "2") (pinfunction "2_2") (pintype "passive"))
    )
    (net (code "23") (name "Net-(LED1-Pad+)") (class "Default")
      (node (ref "LED1") (pin "+") (pinfunction "+_+") (pintype "passive"))
      (node (ref "R7") (pin "1") (pinfunction "1_1") (pintype "passive"))
    )
    (net (code "24") (name "Net-(LED2-Pad+)") (class "Default")
      (node (ref "LED2") (pin "+") (pinfunction "+_+") (pintype "passive"))
      (node (ref "R6") (pin "1") (pinfunction "1_1") (pintype "passive"))
    )
    (net (code "25") (name "Net-(PWR-Pad+)") (class "Default")
      (node (ref "PWR") (pin "+") (pinfunction "+_+") (pintype "passive"))
      (node (ref "R5") (pin "1") (pinfunction "1_1") (pintype "passive"))
    )
    (net (code "26") (name "Net-(S1-2)") (class "Default")
      (node (ref "S1") (pin "B2") (pinfunction "2_B2") (pintype "passive"))
      (node (ref "U$1") (pin "8") (pinfunction "PF4_8") (pintype "bidirectional"))
    )
    (net (code "27") (name "Net-(S2-2)") (class "Default")
      (node (ref "S2") (pin "B2") (pinfunction "2_B2") (pintype "passive"))
      (node (ref "U$1") (pin "7") (pinfunction "PF5_7") (pintype "bidirectional"))
    )
    (net (code "28") (name "Net-(S3-2)") (class "Default")
      (node (ref "S3") (pin "B2") (pinfunction "2_B2") (pintype "passive"))
      (node (ref "U$1") (pin "13") (pinfunction "PA1_13") (pintype "bidirectional"))
    )
    (net (code "29") (name "Net-(S4-2)") (class "Default")
      (node (ref "S4") (pin "B2") (pinfunction "2_B2") (pintype "passive"))
      (node (ref "U$1") (pin "14") (pinfunction "PA0_14") (pintype "bidirectional"))
    )
    (net (code "30") (name "Net-(S5-2)") (class "Default")
      (node (ref "S5") (pin "B2") (pinfunction "2_B2") (pintype "passive"))
      (node (ref "U$1") (pin "4") (pinfunction "PB2_4") (pintype "bidirectional"))
    )
    (net (code "31") (name "Net-(S6-2)") (class "Default")
      (node (ref "S6") (pin "B2") (pinfunction "2_B2") (pintype "passive"))
      (node (ref "U$1") (pin "3") (pinfunction "PB3_3") (pintype "bidirectional"))
    )
    (net (code "32") (name "Net-(U$1-LDO_CAP)") (class "Default")
      (node (ref "C1") (pin "2") (pinfunction "2_2") (pintype "passive"))
      (node (ref "L1") (pin "2") (pinfunction "2_2") (pintype "passive"))
      (node (ref "U$1") (pin "28") (pinfunction "LDO_CAP_28") (pintype "bidirectional"))
    )
    (net (code "33") (name "Net-(U$1-PC0)") (class "Default")
      (node (ref "R6") (pin "2") (pinfunction "2_2") (pintype "passive"))
      (node (ref "U$1") (pin "20") (pinfunction "PC0_20") (pintype "bidirectional"))
    )
    (net (code "34") (name "Net-(U$1-PC1)") (class "Default")
      (node (ref "R7") (pin "2") (pinfunction "2_2") (pintype "passive"))
      (node (ref "U$1") (pin "19") (pinfunction "PC1_19") (pintype "bidirectional"))
    )
    (net (code "35") (name "Net-(U$1-VSW)") (class "Default")
      (node (ref "L1") (pin "1") (pinfunction "1_1") (pintype "passive"))
      (node (ref "U$1") (pin "26") (pinfunction "VSW_26") (pintype "bidirectional"))
    )
    (net (code "36") (name "Net-(U$2-CI)") (class "Default")
      (node (ref "U$2") (pin "C_IN") (pinfunction "CI_C_IN") (pintype "bidirectional"))
      (node (ref "U$33") (pin "CL_OUT") (pinfunction "CO_CL_OUT") (pintype "bidirectional"))
    )
    (net (code "37") (name "Net-(U$2-CO)") (class "Default")
      (node (ref "U$2") (pin "CL_OUT") (pinfunction "CO_CL_OUT") (pintype "bidirectional"))
      (node (ref "U$4") (pin "C_IN") (pinfunction "CI_C_IN") (pintype "bidirectional"))
    )
    (net (code "38") (name "Net-(U$2-DI)") (class "Default")
      (node (ref "U$2") (pin "D_IN") (pinfunction "DI_D_IN") (pintype "bidirectional"))
      (node (ref "U$33") (pin "D_OUT") (pinfunction "DO_D_OUT") (pintype "bidirectional"))
    )
    (net (code "39") (name "Net-(U$2-DO)") (class "Default")
      (node (ref "U$2") (pin "D_OUT") (pinfunction "DO_D_OUT") (pintype "bidirectional"))
      (node (ref "U$4") (pin "D_IN") (pinfunction "DI_D_IN") (pintype "bidirectional"))
    )
    (net (code "40") (name "Net-(U$4-CO)") (class "Default")
      (node (ref "U$4") (pin "CL_OUT") (pinfunction "CO_CL_OUT") (pintype "bidirectional"))
      (node (ref "U$5") (pin "C_IN") (pinfunction "CI_C_IN") (pintype "bidirectional"))
    )
    (net (code "41") (name "Net-(U$4-DO)") (class "Default")
      (node (ref "U$4") (pin "D_OUT") (pinfunction "DO_D_OUT") (pintype "bidirectional"))
      (node (ref "U$5") (pin "D_IN") (pinfunction "DI_D_IN") (pintype "bidirectional"))
    )
    (net (code "42") (name "Net-(U$5-CO)") (class "Default")
      (node (ref "U$5") (pin "CL_OUT") (pinfunction "CO_CL_OUT") (pintype "bidirectional"))
      (node (ref "U$6") (pin "C_IN") (pinfunction "CI_C_IN") (pintype "bidirectional"))
    )
    (net (code "43") (name "Net-(U$5-DO)") (class "Default")
      (node (ref "U$5") (pin "D_OUT") (pinfunction "DO_D_OUT") (pintype "bidirectional"))
      (node (ref "U$6") (pin "D_IN") (pinfunction "DI_D_IN") (pintype "bidirectional"))
    )
    (net (code "44") (name "Net-(U$6-CO)") (class "Default")
      (node (ref "U$6") (pin "CL_OUT") (pinfunction "CO_CL_OUT") (pintype "bidirectional"))
      (node (ref "U$7") (pin "C_IN") (pinfunction "CI_C_IN") (pintype "bidirectional"))
    )
    (net (code "45") (name "Net-(U$6-DO)") (class "Default")
      (node (ref "U$6") (pin "D_OUT") (pinfunction "DO_D_OUT") (pintype "bidirectional"))
      (node (ref "U$7") (pin "D_IN") (pinfunction "DI_D_IN") (pintype "bidirectional"))
    )
    (net (code "46") (name "Net-(U$7-CO)") (class "Default")
      (node (ref "U$7") (pin "CL_OUT") (pinfunction "CO_CL_OUT") (pintype "bidirectional"))
      (node (ref "U$8") (pin "C_IN") (pinfunction "CI_C_IN") (pintype "bidirectional"))
    )
    (net (code "47") (name "Net-(U$7-DO)") (class "Default")
      (node (ref "U$7") (pin "D_OUT") (pinfunction "DO_D_OUT") (pintype "bidirectional"))
      (node (ref "U$8") (pin "D_IN") (pinfunction "DI_D_IN") (pintype "bidirectional"))
    )
    (net (code "48") (name "Net-(U$8-CO)") (class "Default")
      (node (ref "U$8") (pin "CL_OUT") (pinfunction "CO_CL_OUT") (pintype "bidirectional"))
      (node (ref "U$9") (pin "C_IN") (pinfunction "CI_C_IN") (pintype "bidirectional"))
    )
    (net (code "49") (name "Net-(U$8-DO)") (class "Default")
      (node (ref "U$8") (pin "D_OUT") (pinfunction "DO_D_OUT") (pintype "bidirectional"))
      (node (ref "U$9") (pin "D_IN") (pinfunction "DI_D_IN") (pintype "bidirectional"))
    )
    (net (code "50") (name "Net-(U$10-CI)") (class "Default")
      (node (ref "U$10") (pin "C_IN") (pinfunction "CI_C_IN") (pintype "bidirectional"))
      (node (ref "U$9") (pin "CL_OUT") (pinfunction "CO_CL_OUT") (pintype "bidirectional"))
    )
    (net (code "51") (name "Net-(U$10-CO)") (class "Default")
      (node (ref "U$10") (pin "CL_OUT") (pinfunction "CO_CL_OUT") (pintype "bidirectional"))
      (node (ref "U$11") (pin "C_IN") (pinfunction "CI_C_IN") (pintype "bidirectional"))
    )
    (net (code "52") (name "Net-(U$10-DI)") (class "Default")
      (node (ref "U$10") (pin "D_IN") (pinfunction "DI_D_IN") (pintype "bidirectional"))
      (node (ref "U$9") (pin "D_OUT") (pinfunction "DO_D_OUT") (pintype "bidirectional"))
    )
    (net (code "53") (name "Net-(U$10-DO)") (class "Default")
      (node (ref "U$10") (pin "D_OUT") (pinfunction "DO_D_OUT") (pintype "bidirectional"))
      (node (ref "U$11") (pin "D_IN") (pinfunction "DI_D_IN") (pintype "bidirectional"))
    )
    (net (code "54") (name "Net-(U$11-CO)") (class "Default")
      (node (ref "U$11") (pin "CL_OUT") (pinfunction "CO_CL_OUT") (pintype "bidirectional"))
      (node (ref "U$12") (pin "C_IN") (pinfunction "CI_C_IN") (pintype "bidirectional"))
    )
    (net (code "55") (name "Net-(U$11-DO)") (class "Default")
      (node (ref "U$11") (pin "D_OUT") (pinfunction "DO_D_OUT") (pintype "bidirectional"))
      (node (ref "U$12") (pin "D_IN") (pinfunction "DI_D_IN") (pintype "bidirectional"))
    )
    (net (code "56") (name "Net-(U$12-CO)") (class "Default")
      (node (ref "U$12") (pin "CL_OUT") (pinfunction "CO_CL_OUT") (pintype "bidirectional"))
      (node (ref "U$13") (pin "C_IN") (pinfunction "CI_C_IN") (pintype "bidirectional"))
    )
    (net (code "57") (name "Net-(U$12-DO)") (class "Default")
      (node (ref "U$12") (pin "D_OUT") (pinfunction "DO_D_OUT") (pintype "bidirectional"))
      (node (ref "U$13") (pin "D_IN") (pinfunction "DI_D_IN") (pintype "bidirectional"))
    )
    (net (code "58") (name "Net-(U$13-CO)") (class "Default")
      (node (ref "U$13") (pin "CL_OUT") (pinfunction "CO_CL_OUT") (pintype "bidirectional"))
      (node (ref "U$14") (pin "C_IN") (pinfunction "CI_C_IN") (pintype "bidirectional"))
    )
    (net (code "59") (name "Net-(U$13-DO)") (class "Default")
      (node (ref "U$13") (pin "D_OUT") (pinfunction "DO_D_OUT") (pintype "bidirectional"))
      (node (ref "U$14") (pin "D_IN") (pinfunction "DI_D_IN") (pintype "bidirectional"))
    )
    (net (code "60") (name "Net-(U$14-CO)") (class "Default")
      (node (ref "U$14") (pin "CL_OUT") (pinfunction "CO_CL_OUT") (pintype "bidirectional"))
      (node (ref "U$15") (pin "C_IN") (pinfunction "CI_C_IN") (pintype "bidirectional"))
    )
    (net (code "61") (name "Net-(U$14-DO)") (class "Default")
      (node (ref "U$14") (pin "D_OUT") (pinfunction "DO_D_OUT") (pintype "bidirectional"))
      (node (ref "U$15") (pin "D_IN") (pinfunction "DI_D_IN") (pintype "bidirectional"))
    )
    (net (code "62") (name "Net-(U$15-CO)") (class "Default")
      (node (ref "U$15") (pin "CL_OUT") (pinfunction "CO_CL_OUT") (pintype "bidirectional"))
      (node (ref "U$16") (pin "C_IN") (pinfunction "CI_C_IN") (pintype "bidirectional"))
    )
    (net (code "63") (name "Net-(U$15-DO)") (class "Default")
      (node (ref "U$15") (pin "D_OUT") (pinfunction "DO_D_OUT") (pintype "bidirectional"))
      (node (ref "U$16") (pin "D_IN") (pinfunction "DI_D_IN") (pintype "bidirectional"))
    )
    (net (code "64") (name "Net-(U$16-CO)") (class "Default")
      (node (ref "U$16") (pin "CL_OUT") (pinfunction "CO_CL_OUT") (pintype "bidirectional"))
      (node (ref "U$17") (pin "C_IN") (pinfunction "CI_C_IN") (pintype "bidirectional"))
    )
    (net (code "65") (name "Net-(U$16-DO)") (class "Default")
      (node (ref "U$16") (pin "D_OUT") (pinfunction "DO_D_OUT") (pintype "bidirectional"))
      (node (ref "U$17") (pin "D_IN") (pinfunction "DI_D_IN") (pintype "bidirectional"))
    )
    (net (code "66") (name "Net-(U$17-CO)") (class "Default")
      (node (ref "U$17") (pin "CL_OUT") (pinfunction "CO_CL_OUT") (pintype "bidirectional"))
      (node (ref "U$18") (pin "C_IN") (pinfunction "CI_C_IN") (pintype "bidirectional"))
    )
    (net (code "67") (name "Net-(U$17-DO)") (class "Default")
      (node (ref "U$17") (pin "D_OUT") (pinfunction "DO_D_OUT") (pintype "bidirectional"))
      (node (ref "U$18") (pin "D_IN") (pinfunction "DI_D_IN") (pintype "bidirectional"))
    )
    (net (code "68") (name "Net-(U$18-CO)") (class "Default")
      (node (ref "U$18") (pin "CL_OUT") (pinfunction "CO_CL_OUT") (pintype "bidirectional"))
      (node (ref "U$19") (pin "C_IN") (pinfunction "CI_C_IN") (pintype "bidirectional"))
    )
    (net (code "69") (name "Net-(U$18-DO)") (class "Default")
      (node (ref "U$18") (pin "D_OUT") (pinfunction "DO_D_OUT") (pintype "bidirectional"))
      (node (ref "U$19") (pin "D_IN") (pinfunction "DI_D_IN") (pintype "bidirectional"))
    )
    (net (code "70") (name "Net-(U$19-CO)") (class "Default")
      (node (ref "U$19") (pin "CL_OUT") (pinfunction "CO_CL_OUT") (pintype "bidirectional"))
      (node (ref "U$20") (pin "C_IN") (pinfunction "CI_C_IN") (pintype "bidirectional"))
    )
    (net (code "71") (name "Net-(U$19-DO)") (class "Default")
      (node (ref "U$19") (pin "D_OUT") (pinfunction "DO_D_OUT") (pintype "bidirectional"))
      (node (ref "U$20") (pin "D_IN") (pinfunction "DI_D_IN") (pintype "bidirectional"))
    )
    (net (code "72") (name "Net-(U$20-CO)") (class "Default")
      (node (ref "U$20") (pin "CL_OUT") (pinfunction "CO_CL_OUT") (pintype "bidirectional"))
      (node (ref "U$21") (pin "C_IN") (pinfunction "CI_C_IN") (pintype "bidirectional"))
    )
    (net (code "73") (name "Net-(U$20-DO)") (class "Default")
      (node (ref "U$20") (pin "D_OUT") (pinfunction "DO_D_OUT") (pintype "bidirectional"))
      (node (ref "U$21") (pin "D_IN") (pinfunction "DI_D_IN") (pintype "bidirectional"))
    )
    (net (code "74") (name "Net-(U$21-CO)") (class "Default")
      (node (ref "U$21") (pin "CL_OUT") (pinfunction "CO_CL_OUT") (pintype "bidirectional"))
      (node (ref "U$22") (pin "C_IN") (pinfunction "CI_C_IN") (pintype "bidirectional"))
    )
    (net (code "75") (name "Net-(U$21-DO)") (class "Default")
      (node (ref "U$21") (pin "D_OUT") (pinfunction "DO_D_OUT") (pintype "bidirectional"))
      (node (ref "U$22") (pin "D_IN") (pinfunction "DI_D_IN") (pintype "bidirectional"))
    )
    (net (code "76") (name "Net-(U$22-CO)") (class "Default")
      (node (ref "U$22") (pin "CL_OUT") (pinfunction "CO_CL_OUT") (pintype "bidirectional"))
      (node (ref "U$23") (pin "C_IN") (pinfunction "CI_C_IN") (pintype "bidirectional"))
    )
    (net (code "77") (name "Net-(U$22-DO)") (class "Default")
      (node (ref "U$22") (pin "D_OUT") (pinfunction "DO_D_OUT") (pintype "bidirectional"))
      (node (ref "U$23") (pin "D_IN") (pinfunction "DI_D_IN") (pintype "bidirectional"))
    )
    (net (code "78") (name "Net-(U$23-CO)") (class "Default")
      (node (ref "U$23") (pin "CL_OUT") (pinfunction "CO_CL_OUT") (pintype "bidirectional"))
      (node (ref "U$24") (pin "C_IN") (pinfunction "CI_C_IN") (pintype "bidirectional"))
    )
    (net (code "79") (name "Net-(U$23-DO)") (class "Default")
      (node (ref "U$23") (pin "D_OUT") (pinfunction "DO_D_OUT") (pintype "bidirectional"))
      (node (ref "U$24") (pin "D_IN") (pinfunction "DI_D_IN") (pintype "bidirectional"))
    )
    (net (code "80") (name "Net-(U$24-CO)") (class "Default")
      (node (ref "U$24") (pin "CL_OUT") (pinfunction "CO_CL_OUT") (pintype "bidirectional"))
      (node (ref "U$25") (pin "C_IN") (pinfunction "CI_C_IN") (pintype "bidirectional"))
    )
    (net (code "81") (name "Net-(U$24-DO)") (class "Default")
      (node (ref "U$24") (pin "D_OUT") (pinfunction "DO_D_OUT") (pintype "bidirectional"))
      (node (ref "U$25") (pin "D_IN") (pinfunction "DI_D_IN") (pintype "bidirectional"))
    )
    (net (code "82") (name "Net-(U1-IN)") (class "Default")
      (node (ref "C6") (pin "2") (pinfunction "2_2") (pintype "passive"))
      (node (ref "D1") (pin "-") (pinfunction "-_-") (pintype "passive"))
      (node (ref "D2") (pin "-") (pinfunction "-_-") (pintype "passive"))
      (node (ref "U1") (pin "3") (pinfunction "IN_3") (pintype "input"))
    )
    (net (code "83") (name "V_USB") (class "Default")
      (node (ref "D2") (pin "+") (pinfunction "+_+") (pintype "passive"))
      (node (ref "J1") (pin "1") (pinfunction "VCC_1") (pintype "bidirectional"))
      (node (ref "R4") (pin "2") (pinfunction "2_2") (pintype "passive"))
    )
    (net (code "84") (name "unconnected-(U$1-PB12-Pad31)") (class "Default")
      (node (ref "U$1") (pin "31") (pinfunction "PB12_31") (pintype "bidirectional"))
    )
    (net (code "85") (name "unconnected-(U$1-PB13-Pad30)") (class "Default")
      (node (ref "U$1") (pin "30") (pinfunction "PB13_30") (pintype "bidirectional"))
    )
    (net (code "86") (name "unconnected-(U$1-PB14-Pad29)") (class "Default")
      (node (ref "U$1") (pin "29") (pinfunction "PB14_29") (pintype "bidirectional"))
    )
    (net (code "87") (name "unconnected-(U$25-CO-PadCL_OUT)") (class "Default")
      (node (ref "U$25") (pin "CL_OUT") (pinfunction "CO_CL_OUT") (pintype "bidirectional"))
    )
    (net (code "88") (name "unconnected-(U$25-DO-PadD_OUT)") (class "Default")
      (node (ref "U$25") (pin "D_OUT") (pinfunction "DO_D_OUT") (pintype "bidirectional"))
    )
  )
)
